# pCog103_Wifi_Keyboard_TFT.net
KiCad netlist of a schematic drawn in EAGLE
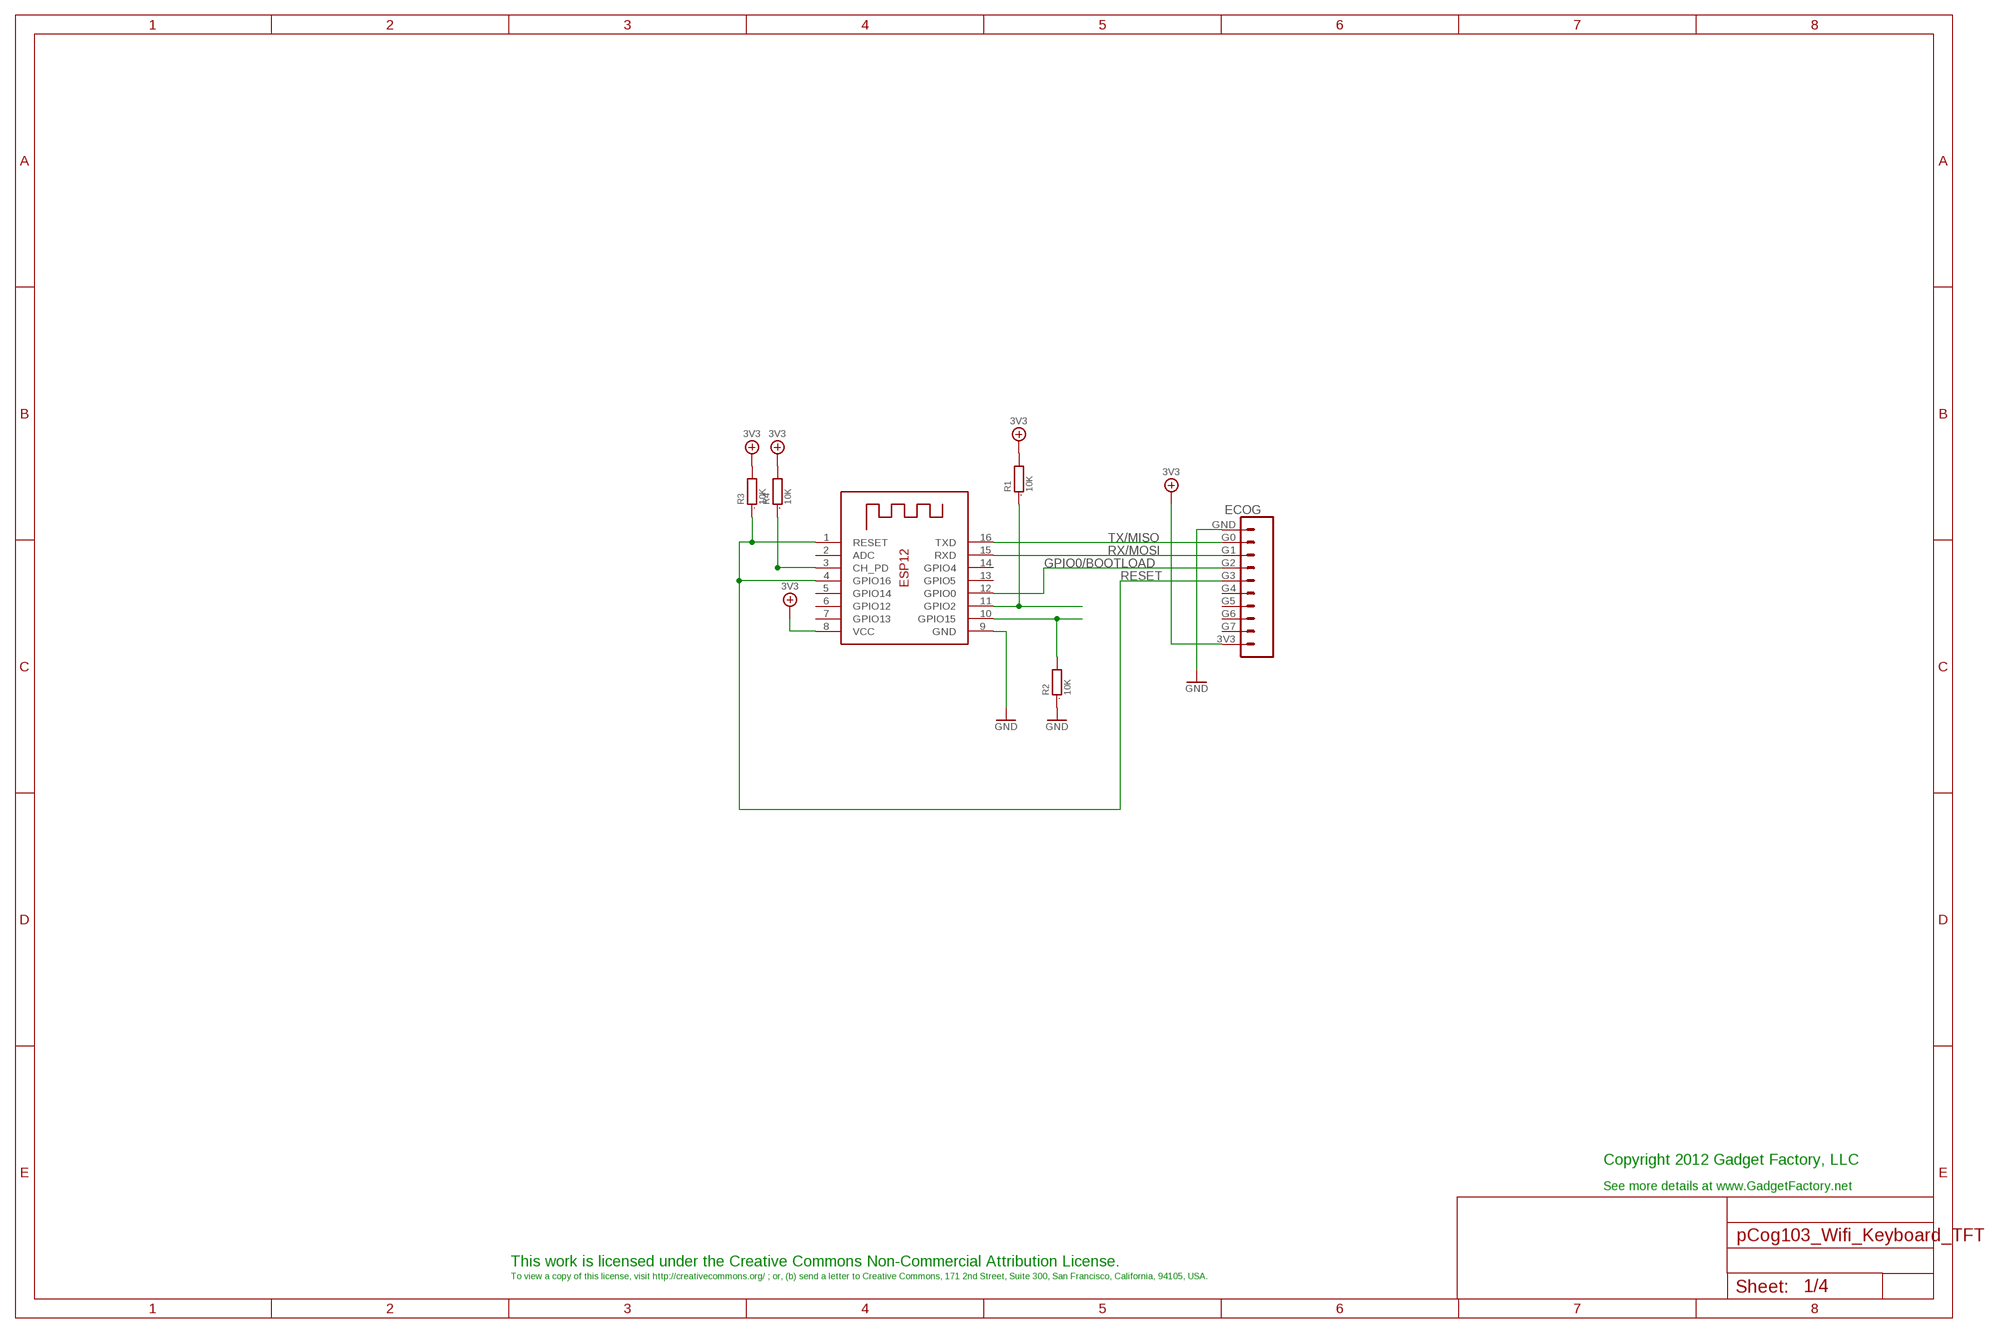
[diagram p0: schematic, sheet 1]
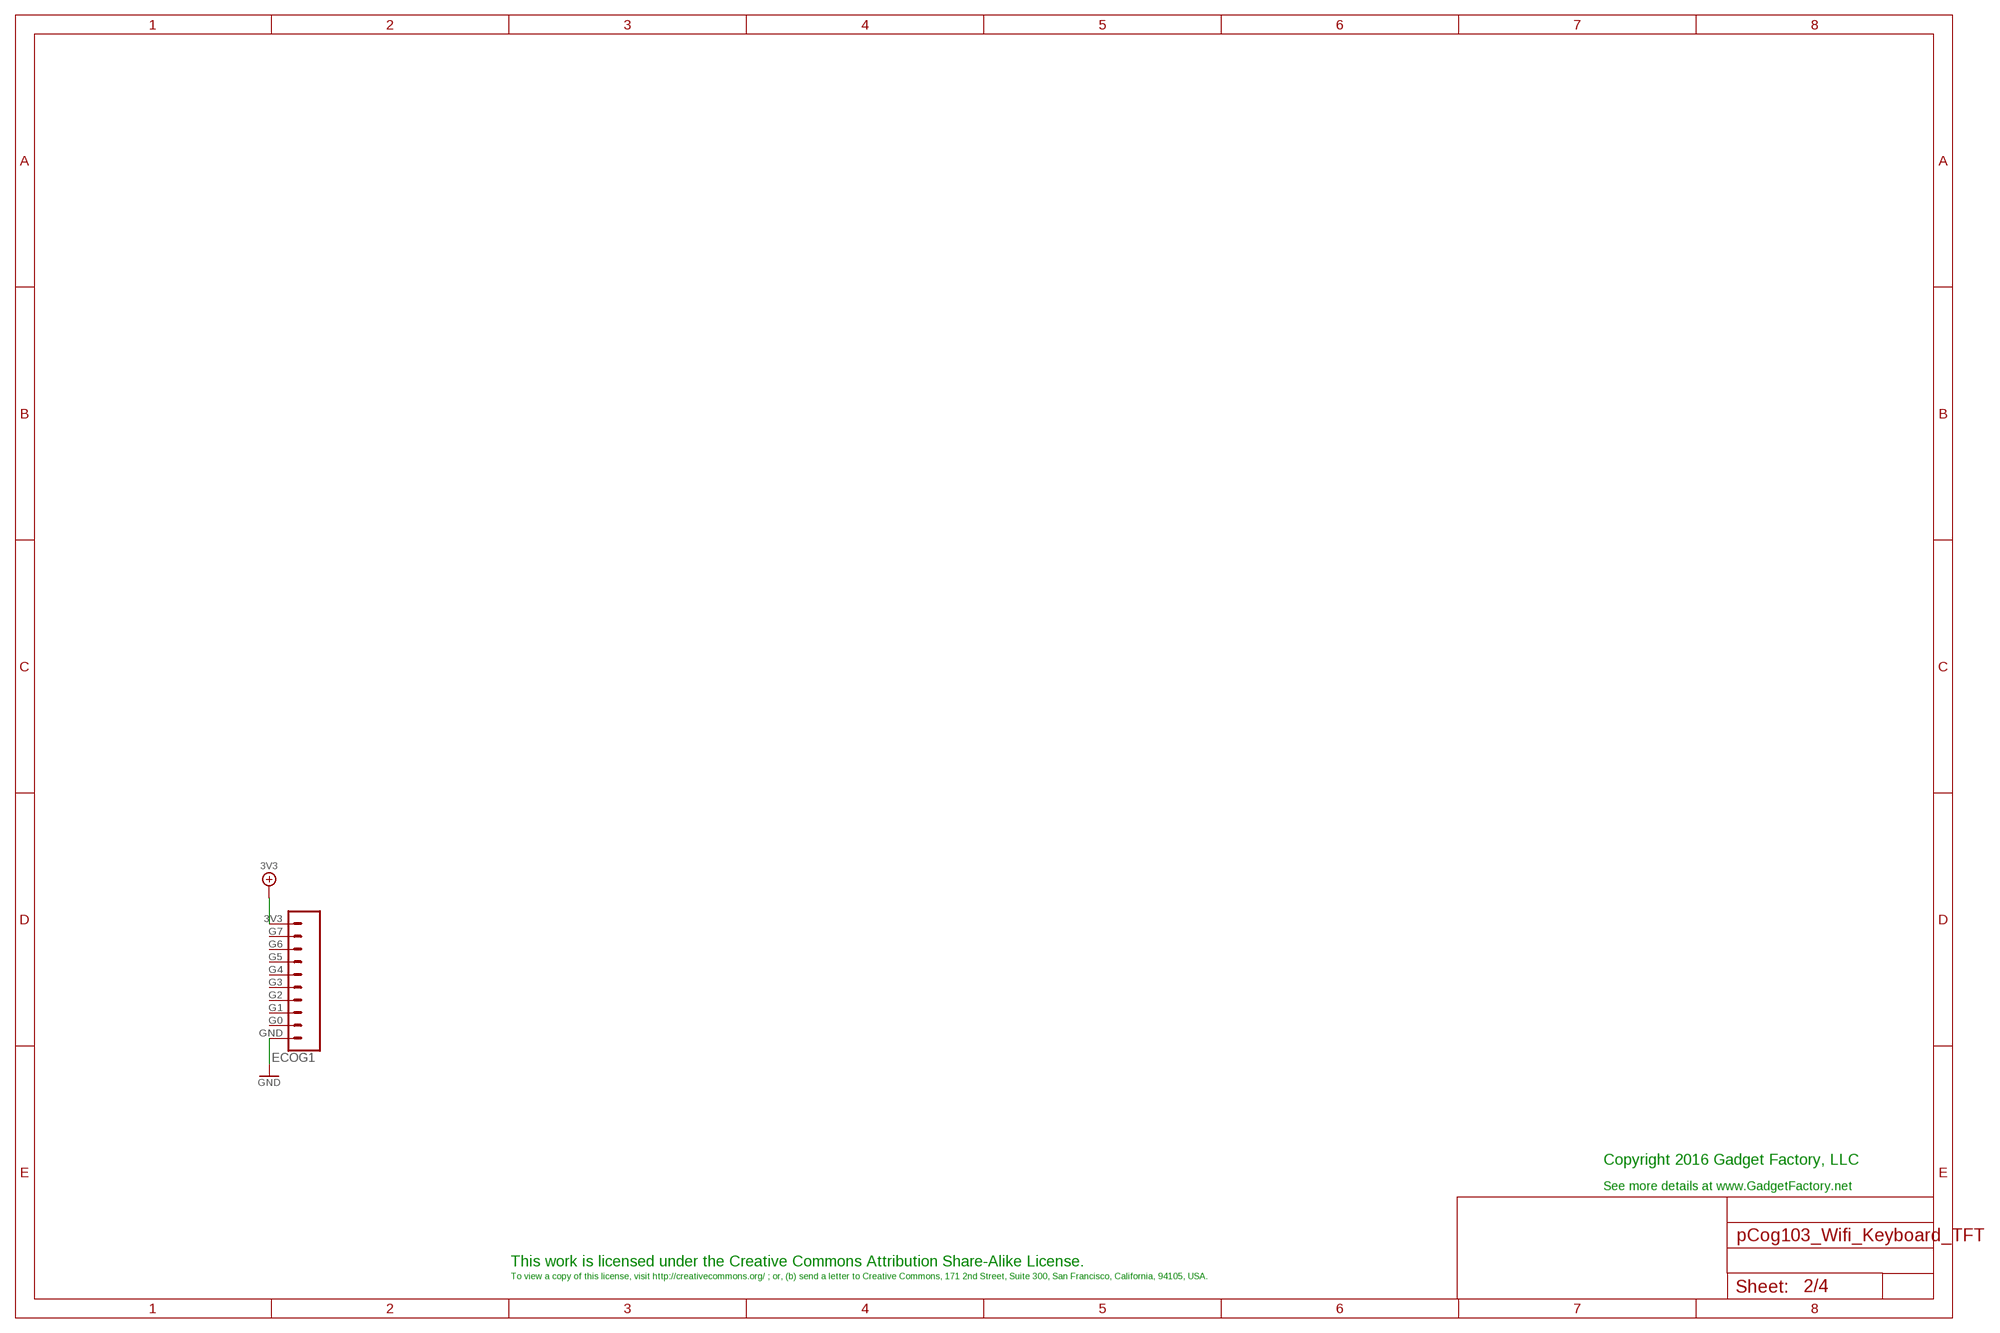
[diagram p1: schematic, sheet 2]
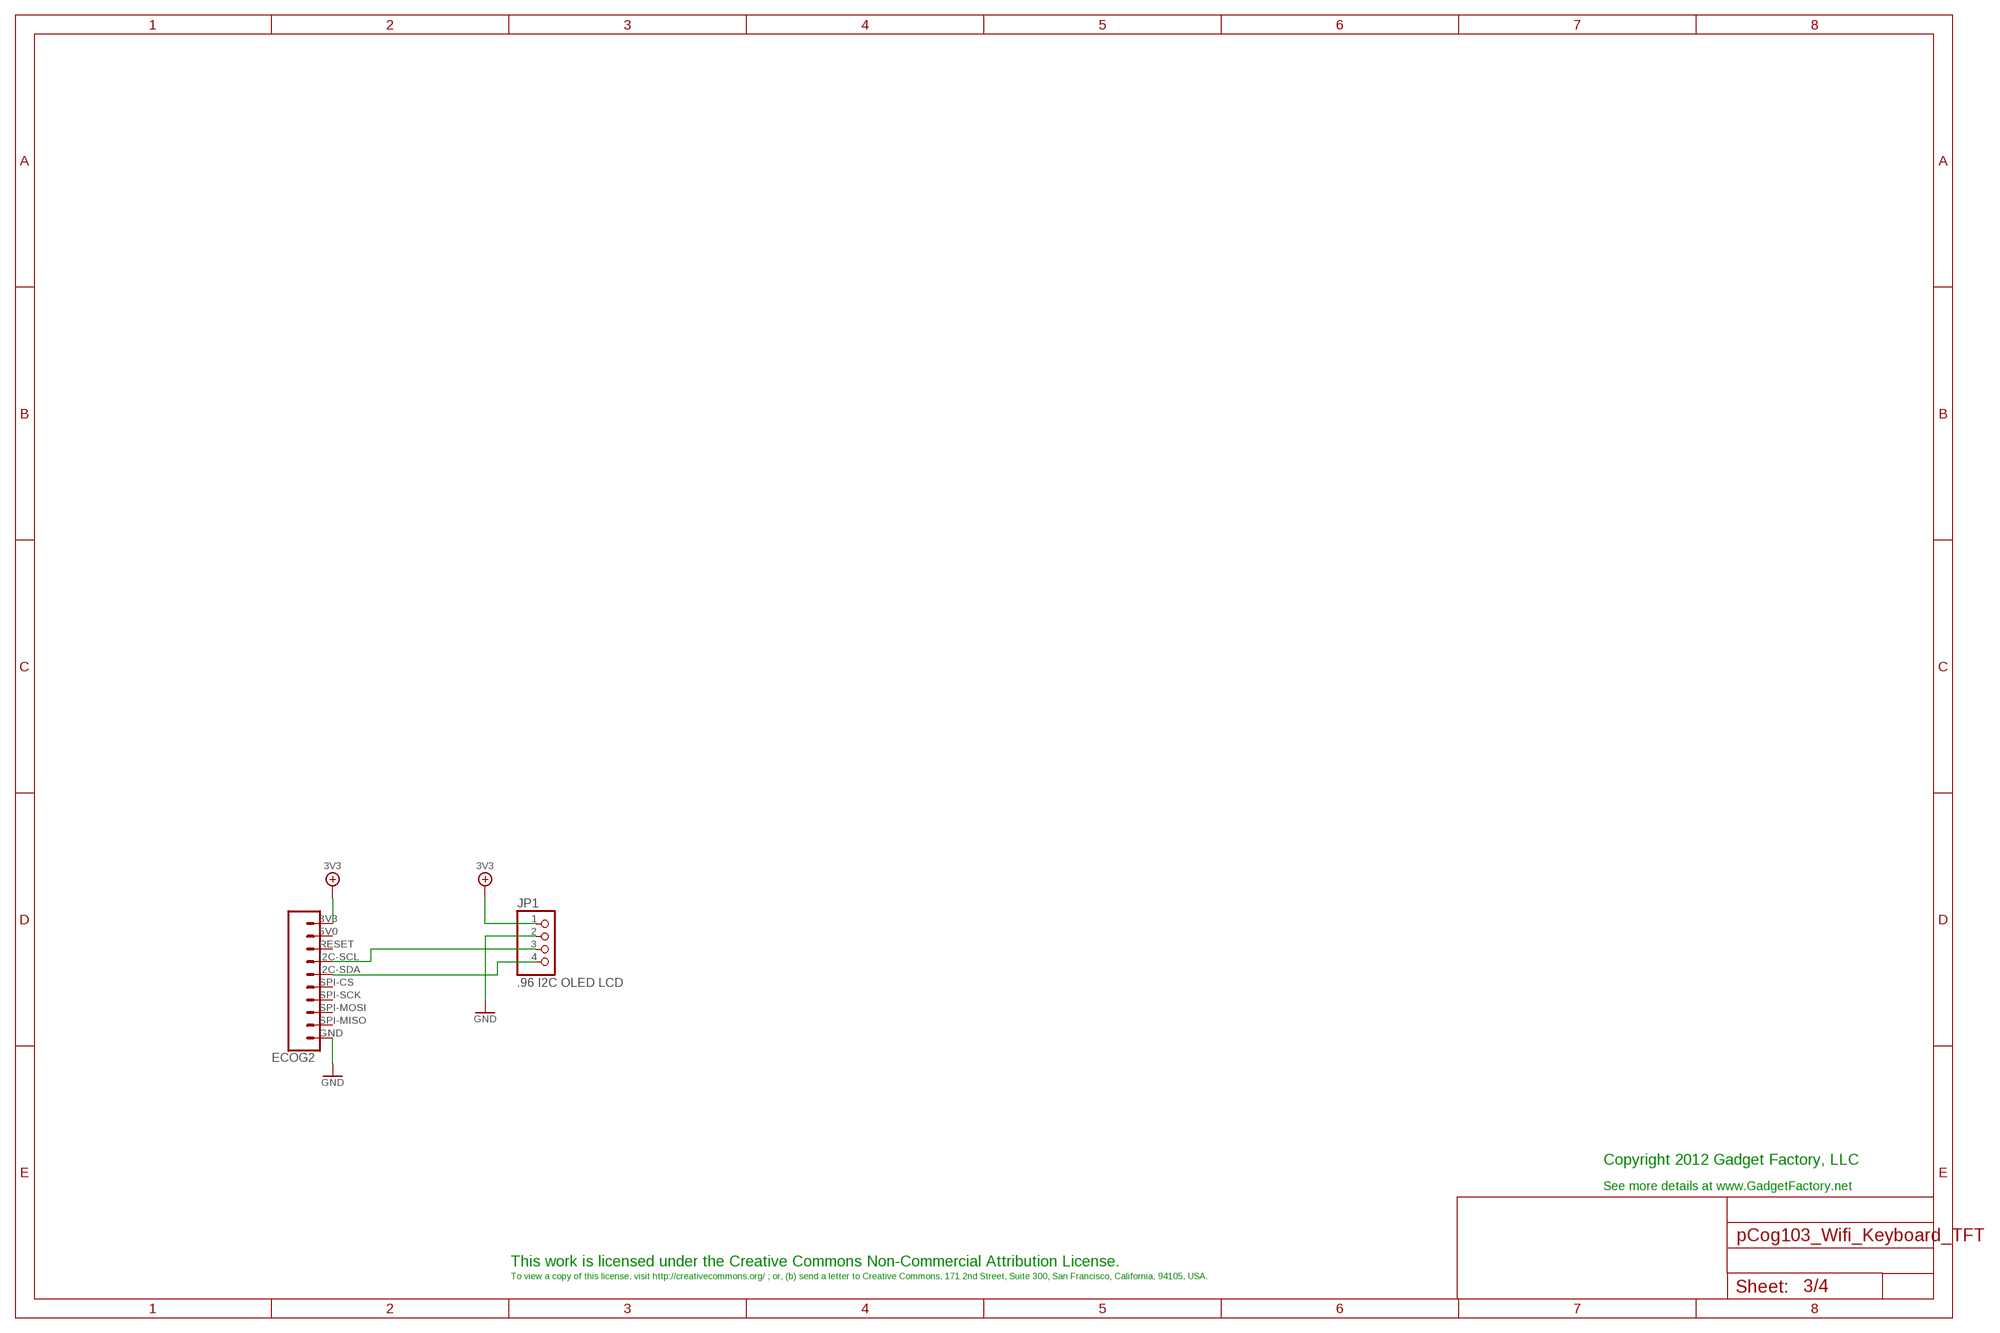
[diagram p2: schematic, sheet 3]
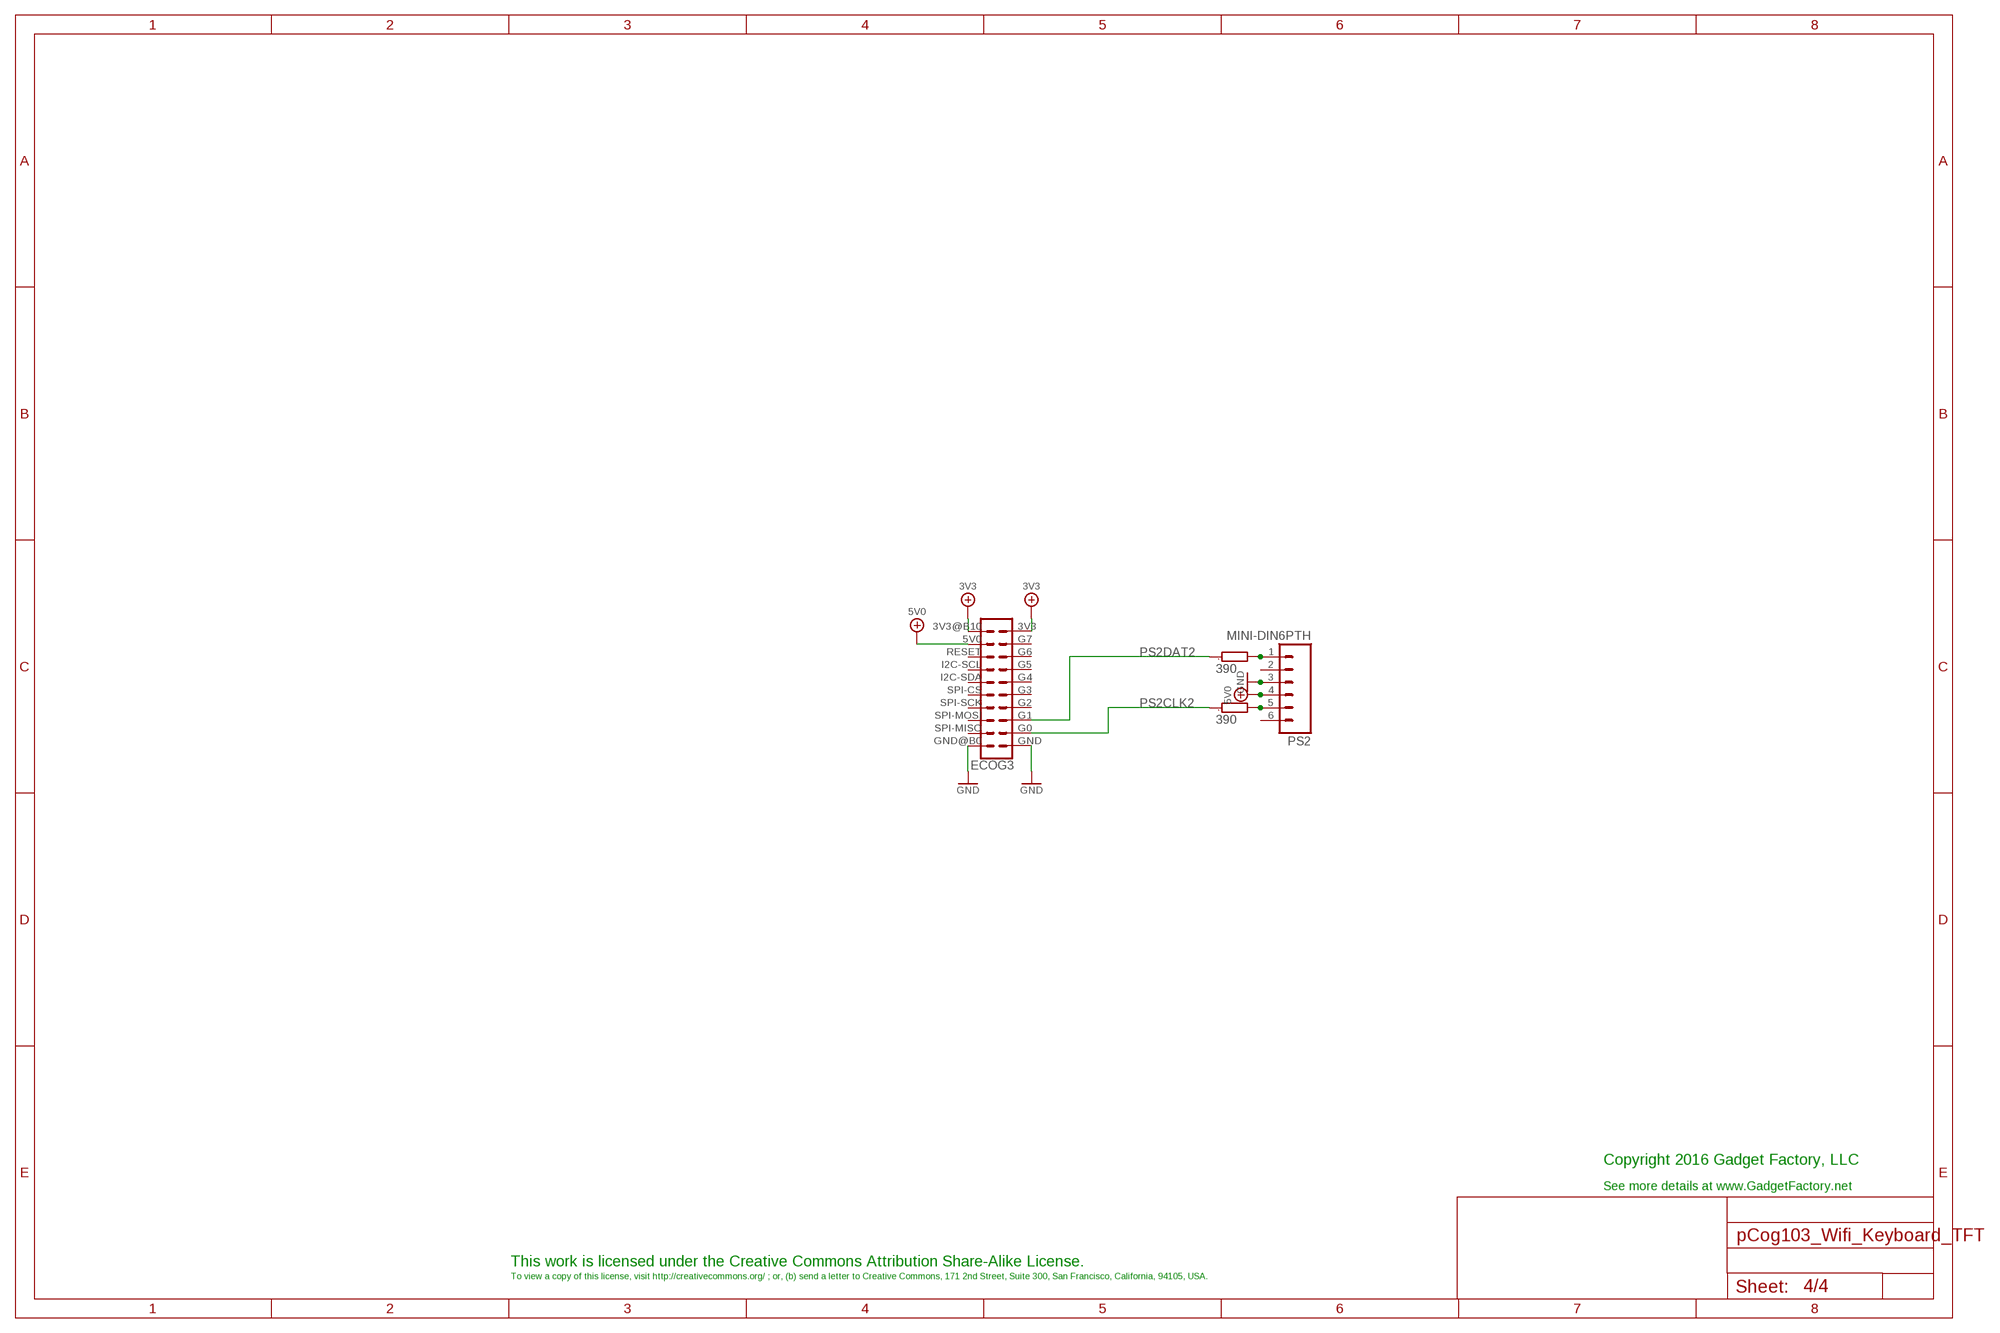
[diagram p3: schematic, sheet 4]

(export (version "E")
  (design (tool "Eeschema 10.0.6"))
  (components
    (comp (ref "ECOG1")
      (value "ECOG_GENERAL_ROWSURFACEMOUNT")
      (footprint "eagle-import:ECOG_GENERAL_SMD")
      (libsource (lib "eagle-import") (part "ECOG_GENERAL_ROWSURFACEMOUNT"))
    )
    (comp (ref "ECOG")
      (value "ECOG_GENERAL_ROWTHROUGHOLE")
      (footprint "eagle-import:ECOG_GENERAL_TH")
      (libsource (lib "eagle-import") (part "ECOG_GENERAL_ROWTHROUGHOLE"))
    )
    (comp (ref "R1")
      (value "10K")
      (footprint "eagle-import:0805")
      (libsource (lib "eagle-import") (part "R0805"))
    )
    (comp (ref "R2")
      (value "10K")
      (footprint "eagle-import:0805")
      (libsource (lib "eagle-import") (part "R0805"))
    )
    (comp (ref "R3")
      (value "10K")
      (footprint "eagle-import:0805")
      (libsource (lib "eagle-import") (part "R0805"))
    )
    (comp (ref "R4")
      (value "10K")
      (footprint "eagle-import:0805")
      (libsource (lib "eagle-import") (part "R0805"))
    )
    (comp (ref "X1")
      (value "ESP-12")
      (footprint "eagle-import:ESP-12")
      (libsource (lib "eagle-import") (part "ESP-12"))
    )
    (comp (ref "ECOG2")
      (value "ECOG_BUSES_ROWTHROUGHHOLE")
      (footprint "eagle-import:ECOG_BUSES_TH")
      (libsource (lib "eagle-import") (part "ECOG_BUSES_ROWTHROUGHHOLE"))
    )
    (comp (ref "JP1")
      (value ".96 I2C OLED LCD")
      (footprint "eagle-import:1X04")
      (libsource (lib "eagle-import") (part "PINHD-1X4"))
    )
    (comp (ref "ECOG3")
      (value "ECOG_DUALTHROUGHHOLE")
      (footprint "eagle-import:ECOG_DUAL_TH")
      (libsource (lib "eagle-import") (part "ECOG_DUALTHROUGHHOLE"))
    )
    (comp (ref "PS2")
      (value "MINI-DIN6PTH")
      (footprint "eagle-import:MINI-DIN6")
      (libsource (lib "eagle-import") (part "MINI-DIN6PTH"))
    )
    (comp (ref "R5")
      (value "390")
      (footprint "eagle-import:0603")
      (libsource (lib "eagle-import") (part "R0603"))
    )
    (comp (ref "R6")
      (value "390")
      (footprint "eagle-import:0603")
      (libsource (lib "eagle-import") (part "R0603"))
    )
  )
  (nets
    (net (code "1") (name "3V3") (class "Default")
      (node (ref "ECOG") (pin "3V3") (pinfunction "3V3_3V3") (pintype "power_in"))
      (node (ref "ECOG1") (pin "3V3") (pinfunction "3V3_3V3") (pintype "power_in"))
      (node (ref "ECOG2") (pin "3V3") (pinfunction "3V3_3V3") (pintype "passive"))
      (node (ref "ECOG3") (pin "3V3") (pinfunction "3V3_3V3") (pintype "passive"))
      (node (ref "ECOG3") (pin "3V3@B10") (pinfunction "3V3_3V3@B10") (pintype "passive"))
      (node (ref "JP1") (pin "1") (pinfunction "1_1") (pintype "passive"))
      (node (ref "R1") (pin "2") (pinfunction "2_2") (pintype "passive"))
      (node (ref "R3") (pin "2") (pinfunction "2_2") (pintype "passive"))
      (node (ref "R4") (pin "2") (pinfunction "2_2") (pintype "passive"))
      (node (ref "X1") (pin "8") (pinfunction "VCC_8") (pintype "power_in"))
    )
    (net (code "2") (name "5V0") (class "Default")
      (node (ref "ECOG3") (pin "5V0") (pinfunction "5V_5V0") (pintype "passive"))
      (node (ref "PS2") (pin "4") (pinfunction "4_4") (pintype "passive"))
    )
    (net (code "3") (name "GND") (class "Default")
      (node (ref "ECOG") (pin "GND") (pinfunction "GND_GND") (pintype "power_in"))
      (node (ref "ECOG1") (pin "GND") (pinfunction "GND_GND") (pintype "power_in"))
      (node (ref "ECOG2") (pin "GND") (pinfunction "GND_GND") (pintype "passive"))
      (node (ref "ECOG3") (pin "GND") (pinfunction "GND_GND") (pintype "passive"))
      (node (ref "ECOG3") (pin "GND@B0") (pinfunction "GND_GND@B0") (pintype "passive"))
      (node (ref "JP1") (pin "2") (pinfunction "2_2") (pintype "passive"))
      (node (ref "PS2") (pin "3") (pinfunction "3_3") (pintype "passive"))
      (node (ref "R2") (pin "1") (pinfunction "1_1") (pintype "passive"))
      (node (ref "X1") (pin "9") (pinfunction "GND_9") (pintype "power_in"))
    )
    (net (code "4") (name "GPIO0{slash}BOOTLOAD") (class "Default")
      (node (ref "ECOG") (pin "G2") (pinfunction "G2_G2") (pintype "passive"))
      (node (ref "X1") (pin "12") (pinfunction "GPIO0_12") (pintype "bidirectional"))
    )
    (net (code "5") (name "Net-(ECOG2-PadI2C-SCL)") (class "Default")
      (node (ref "ECOG2") (pin "I2C-SCL") (pinfunction "I2C-SCL_I2C-SCL") (pintype "passive"))
      (node (ref "JP1") (pin "3") (pinfunction "3_3") (pintype "passive"))
    )
    (net (code "6") (name "Net-(ECOG2-PadI2C-SDA)") (class "Default")
      (node (ref "ECOG2") (pin "I2C-SDA") (pinfunction "I2C-SDA_I2C-SDA") (pintype "passive"))
      (node (ref "JP1") (pin "4") (pinfunction "4_4") (pintype "passive"))
    )
    (net (code "7") (name "Net-(PS2-Pad1)") (class "Default")
      (node (ref "PS2") (pin "1") (pinfunction "1_1") (pintype "passive"))
      (node (ref "R5") (pin "2") (pinfunction "2_2") (pintype "passive"))
    )
    (net (code "8") (name "Net-(PS2-Pad5)") (class "Default")
      (node (ref "PS2") (pin "5") (pinfunction "5_5") (pintype "passive"))
      (node (ref "R6") (pin "2") (pinfunction "2_2") (pintype "passive"))
    )
    (net (code "9") (name "Net-(X1-CH_PD)") (class "Default")
      (node (ref "R4") (pin "1") (pinfunction "1_1") (pintype "passive"))
      (node (ref "X1") (pin "3") (pinfunction "CH_PD_3") (pintype "input"))
    )
    (net (code "10") (name "Net-(X1-GPIO2)") (class "Default")
      (node (ref "R1") (pin "1") (pinfunction "1_1") (pintype "passive"))
      (node (ref "X1") (pin "11") (pinfunction "GPIO2_11") (pintype "bidirectional"))
    )
    (net (code "11") (name "Net-(X1-GPIO15)") (class "Default")
      (node (ref "R2") (pin "2") (pinfunction "2_2") (pintype "passive"))
      (node (ref "X1") (pin "10") (pinfunction "GPIO15_10") (pintype "bidirectional"))
    )
    (net (code "12") (name "PS2CLK2") (class "Default")
      (node (ref "ECOG3") (pin "G0") (pinfunction "G0_G0") (pintype "passive"))
      (node (ref "R6") (pin "1") (pinfunction "1_1") (pintype "passive"))
    )
    (net (code "13") (name "PS2DAT2") (class "Default")
      (node (ref "ECOG3") (pin "G1") (pinfunction "G1_G1") (pintype "passive"))
      (node (ref "R5") (pin "1") (pinfunction "1_1") (pintype "passive"))
    )
    (net (code "14") (name "RESET") (class "Default")
      (node (ref "ECOG") (pin "G3") (pinfunction "G3_G3") (pintype "passive"))
      (node (ref "R3") (pin "1") (pinfunction "1_1") (pintype "passive"))
      (node (ref "X1") (pin "1") (pinfunction "RESET_1") (pintype "input"))
      (node (ref "X1") (pin "4") (pinfunction "GPIO16_4") (pintype "bidirectional"))
    )
    (net (code "15") (name "RX{slash}MOSI") (class "Default")
      (node (ref "ECOG") (pin "G1") (pinfunction "G1_G1") (pintype "passive"))
      (node (ref "X1") (pin "15") (pinfunction "RXD_15") (pintype "input"))
    )
    (net (code "16") (name "TX{slash}MISO") (class "Default")
      (node (ref "ECOG") (pin "G0") (pinfunction "G0_G0") (pintype "passive"))
      (node (ref "X1") (pin "16") (pinfunction "TXD_16") (pintype "output"))
    )
    (net (code "17") (name "unconnected-(ECOG-PadG4)") (class "Default")
      (node (ref "ECOG") (pin "G4") (pinfunction "G4_G4") (pintype "passive"))
    )
    (net (code "18") (name "unconnected-(ECOG-PadG5)") (class "Default")
      (node (ref "ECOG") (pin "G5") (pinfunction "G5_G5") (pintype "passive"))
    )
    (net (code "19") (name "unconnected-(ECOG-PadG6)") (class "Default")
      (node (ref "ECOG") (pin "G6") (pinfunction "G6_G6") (pintype "passive"))
    )
    (net (code "20") (name "unconnected-(ECOG-PadG7)") (class "Default")
      (node (ref "ECOG") (pin "G7") (pinfunction "G7_G7") (pintype "passive"))
    )
    (net (code "21") (name "unconnected-(ECOG1-PadG0)") (class "Default")
      (node (ref "ECOG1") (pin "G0") (pinfunction "G0_G0") (pintype "passive"))
    )
    (net (code "22") (name "unconnected-(ECOG1-PadG1)") (class "Default")
      (node (ref "ECOG1") (pin "G1") (pinfunction "G1_G1") (pintype "passive"))
    )
    (net (code "23") (name "unconnected-(ECOG1-PadG2)") (class "Default")
      (node (ref "ECOG1") (pin "G2") (pinfunction "G2_G2") (pintype "passive"))
    )
    (net (code "24") (name "unconnected-(ECOG1-PadG3)") (class "Default")
      (node (ref "ECOG1") (pin "G3") (pinfunction "G3_G3") (pintype "passive"))
    )
    (net (code "25") (name "unconnected-(ECOG1-PadG4)") (class "Default")
      (node (ref "ECOG1") (pin "G4") (pinfunction "G4_G4") (pintype "passive"))
    )
    (net (code "26") (name "unconnected-(ECOG1-PadG5)") (class "Default")
      (node (ref "ECOG1") (pin "G5") (pinfunction "G5_G5") (pintype "passive"))
    )
    (net (code "27") (name "unconnected-(ECOG1-PadG6)") (class "Default")
      (node (ref "ECOG1") (pin "G6") (pinfunction "G6_G6") (pintype "passive"))
    )
    (net (code "28") (name "unconnected-(ECOG1-PadG7)") (class "Default")
      (node (ref "ECOG1") (pin "G7") (pinfunction "G7_G7") (pintype "passive"))
    )
    (net (code "29") (name "unconnected-(ECOG2-PadSPI-CS)") (class "Default")
      (node (ref "ECOG2") (pin "SPI-CS") (pinfunction "SPI-CS_SPI-CS") (pintype "passive"))
    )
    (net (code "30") (name "unconnected-(ECOG2-PadSPI-MISO)") (class "Default")
      (node (ref "ECOG2") (pin "SPI-MISO") (pinfunction "SPI-MISO_SPI-MISO") (pintype "passive"))
    )
    (net (code "31") (name "unconnected-(ECOG2-PadSPI-MOSI)") (class "Default")
      (node (ref "ECOG2") (pin "SPI-MOSI") (pinfunction "SPI-MOSI_SPI-MOSI") (pintype "passive"))
    )
    (net (code "32") (name "unconnected-(ECOG2-PadSPI-SCK)") (class "Default")
      (node (ref "ECOG2") (pin "SPI-SCK") (pinfunction "SPI-SCK_SPI-SCK") (pintype "passive"))
    )
    (net (code "33") (name "unconnected-(ECOG2-RSV-Pad5V0)") (class "Default")
      (node (ref "ECOG2") (pin "5V0") (pinfunction "RSV_5V0") (pintype "passive"))
    )
    (net (code "34") (name "unconnected-(ECOG2-RSV-PadRESET)") (class "Default")
      (node (ref "ECOG2") (pin "RESET") (pinfunction "RSV_RESET") (pintype "passive"))
    )
    (net (code "35") (name "unconnected-(ECOG3-PadG2)") (class "Default")
      (node (ref "ECOG3") (pin "G2") (pinfunction "G2_G2") (pintype "passive"))
    )
    (net (code "36") (name "unconnected-(ECOG3-PadG3)") (class "Default")
      (node (ref "ECOG3") (pin "G3") (pinfunction "G3_G3") (pintype "passive"))
    )
    (net (code "37") (name "unconnected-(ECOG3-PadG4)") (class "Default")
      (node (ref "ECOG3") (pin "G4") (pinfunction "G4_G4") (pintype "passive"))
    )
    (net (code "38") (name "unconnected-(ECOG3-PadG5)") (class "Default")
      (node (ref "ECOG3") (pin "G5") (pinfunction "G5_G5") (pintype "passive"))
    )
    (net (code "39") (name "unconnected-(ECOG3-PadG6)") (class "Default")
      (node (ref "ECOG3") (pin "G6") (pinfunction "G6_G6") (pintype "passive"))
    )
    (net (code "40") (name "unconnected-(ECOG3-PadG7)") (class "Default")
      (node (ref "ECOG3") (pin "G7") (pinfunction "G7_G7") (pintype "passive"))
    )
    (net (code "41") (name "unconnected-(ECOG3-PadI2C-SCL)") (class "Default")
      (node (ref "ECOG3") (pin "I2C-SCL") (pinfunction "I2C-SCL_I2C-SCL") (pintype "passive"))
    )
    (net (code "42") (name "unconnected-(ECOG3-PadI2C-SDA)") (class "Default")
      (node (ref "ECOG3") (pin "I2C-SDA") (pinfunction "I2C-SDA_I2C-SDA") (pintype "passive"))
    )
    (net (code "43") (name "unconnected-(ECOG3-PadRESET)") (class "Default")
      (node (ref "ECOG3") (pin "RESET") (pinfunction "RESET_RESET") (pintype "passive"))
    )
    (net (code "44") (name "unconnected-(ECOG3-PadSPI-CS)") (class "Default")
      (node (ref "ECOG3") (pin "SPI-CS") (pinfunction "SPI-CS_SPI-CS") (pintype "passive"))
    )
    (net (code "45") (name "unconnected-(ECOG3-PadSPI-MISO)") (class "Default")
      (node (ref "ECOG3") (pin "SPI-MISO") (pinfunction "SPI-MISO_SPI-MISO") (pintype "passive"))
    )
    (net (code "46") (name "unconnected-(ECOG3-PadSPI-MOSI)") (class "Default")
      (node (ref "ECOG3") (pin "SPI-MOSI") (pinfunction "SPI-MOSI_SPI-MOSI") (pintype "passive"))
    )
    (net (code "47") (name "unconnected-(ECOG3-PadSPI-SCK)") (class "Default")
      (node (ref "ECOG3") (pin "SPI-SCK") (pinfunction "SPI-SCK_SPI-SCK") (pintype "passive"))
    )
    (net (code "48") (name "unconnected-(PS2-Pad2)") (class "Default")
      (node (ref "PS2") (pin "2") (pinfunction "2_2") (pintype "passive"))
    )
    (net (code "49") (name "unconnected-(PS2-Pad6)") (class "Default")
      (node (ref "PS2") (pin "6") (pinfunction "6_6") (pintype "passive"))
    )
    (net (code "50") (name "unconnected-(X1-ADC-Pad2)") (class "Default")
      (node (ref "X1") (pin "2") (pinfunction "ADC_2") (pintype "passive"))
    )
    (net (code "51") (name "unconnected-(X1-GPIO4-Pad14)") (class "Default")
      (node (ref "X1") (pin "14") (pinfunction "GPIO4_14") (pintype "bidirectional"))
    )
    (net (code "52") (name "unconnected-(X1-GPIO5-Pad13)") (class "Default")
      (node (ref "X1") (pin "13") (pinfunction "GPIO5_13") (pintype "bidirectional"))
    )
    (net (code "53") (name "unconnected-(X1-GPIO12-Pad6)") (class "Default")
      (node (ref "X1") (pin "6") (pinfunction "GPIO12_6") (pintype "bidirectional"))
    )
    (net (code "54") (name "unconnected-(X1-GPIO13-Pad7)") (class "Default")
      (node (ref "X1") (pin "7") (pinfunction "GPIO13_7") (pintype "bidirectional"))
    )
    (net (code "55") (name "unconnected-(X1-GPIO14-Pad5)") (class "Default")
      (node (ref "X1") (pin "5") (pinfunction "GPIO14_5") (pintype "bidirectional"))
    )
  )
)
